# xbee_module_jan2022.net
KiCad netlist of a schematic drawn in EAGLE
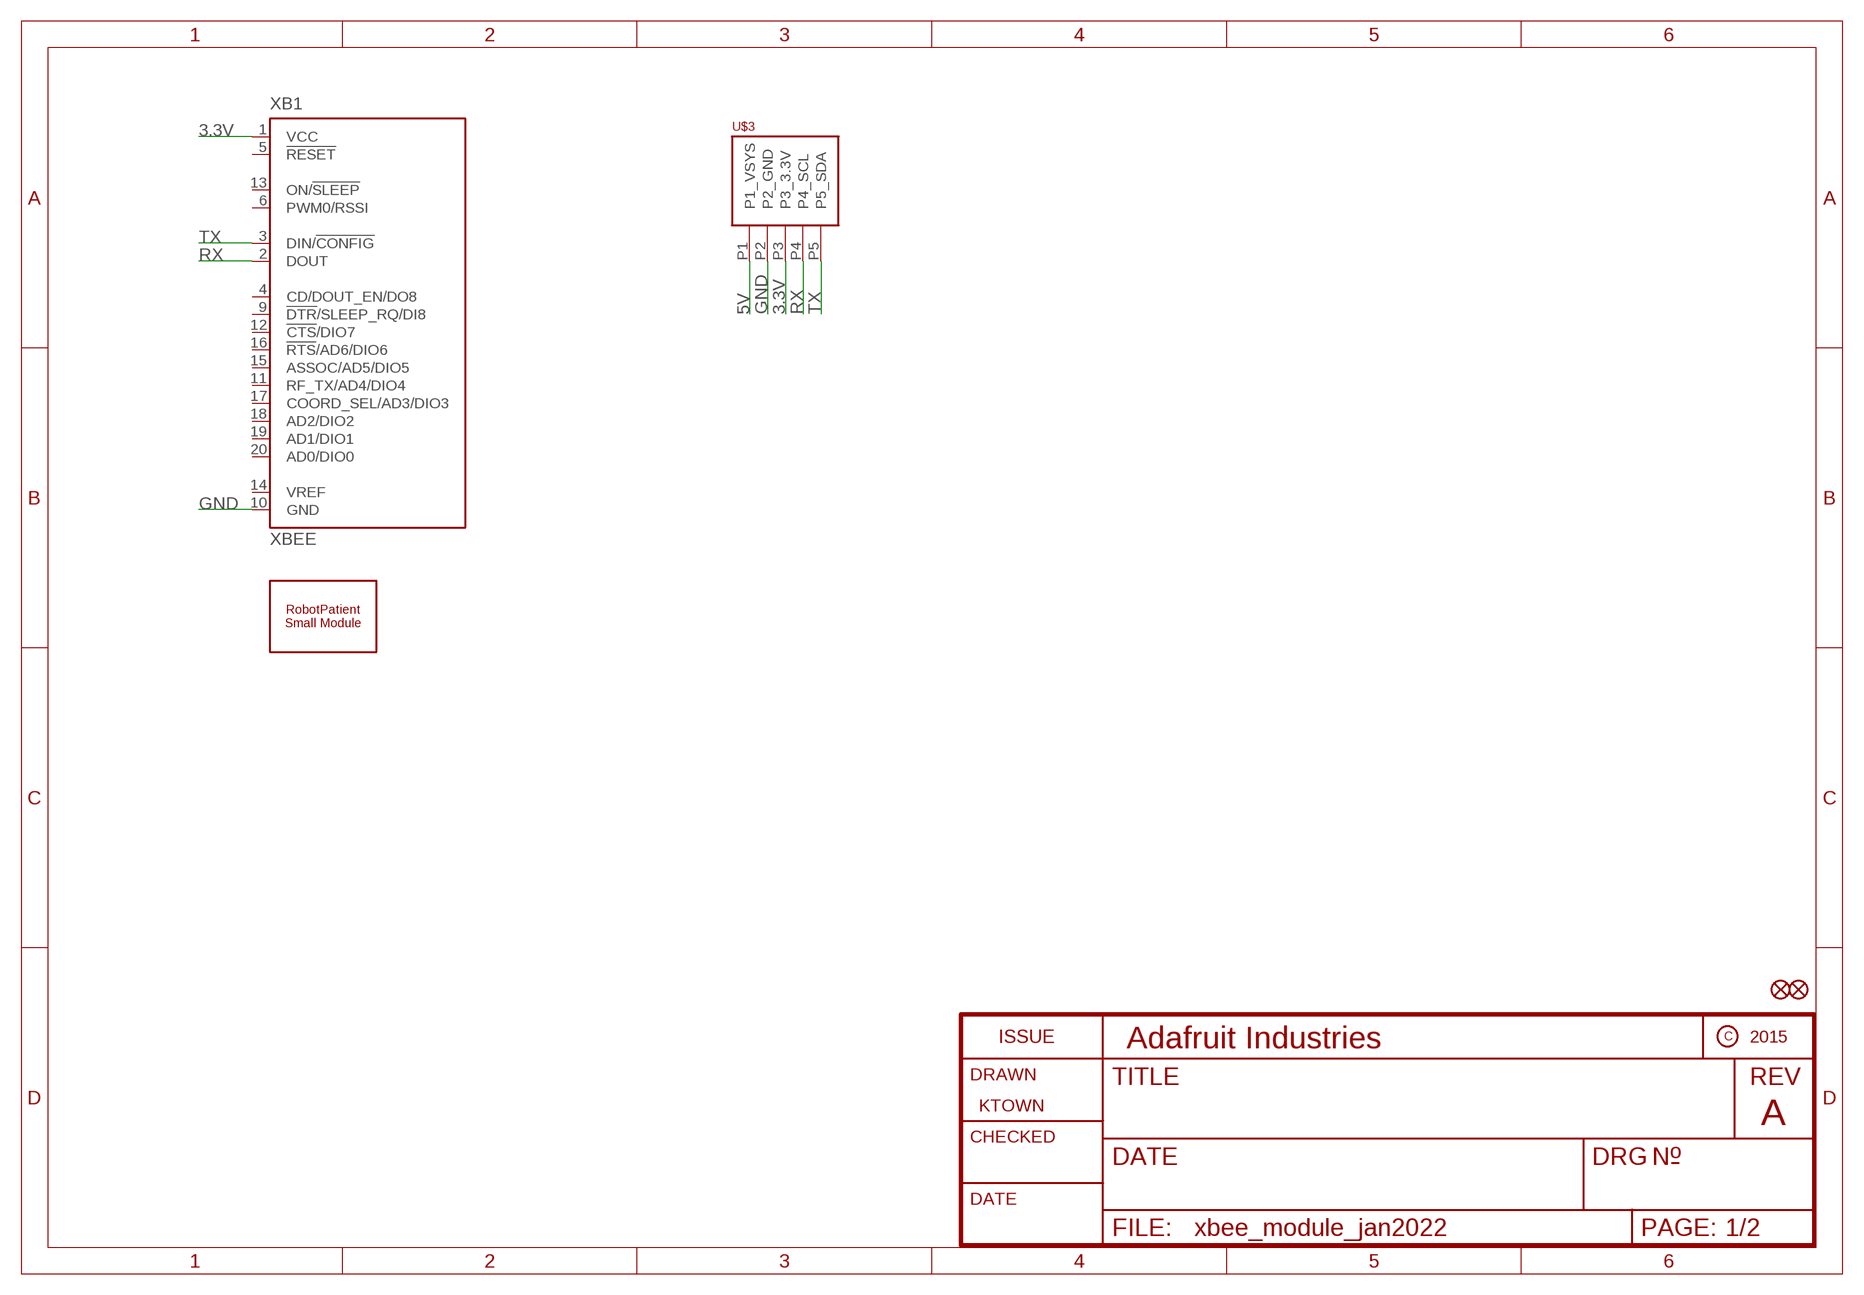
[diagram p0: schematic, sheet 1]
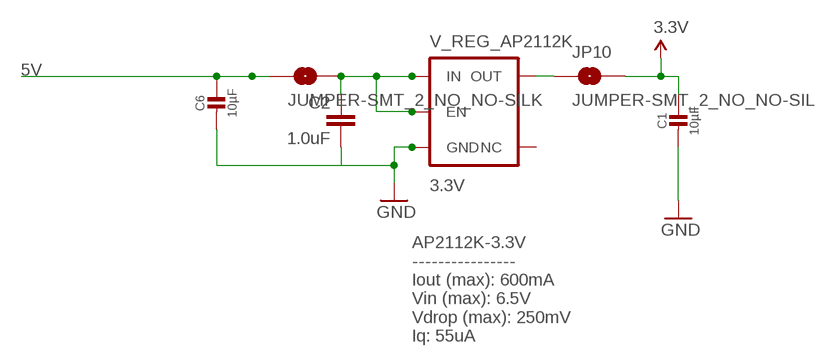
[diagram p1: schematic, sheet 2]

(export (version "E")
  (design (tool "Eeschema 10.0.6"))
  (components
    (comp (ref "FID1")
      (value "FIDUCIAL\"\"")
      (footprint "eagle-import:FIDUCIAL_1MM")
      (libsource (lib "eagle-import") (part "FIDUCIAL{dblquote}{dblquote}"))
    )
    (comp (ref "FID2")
      (value "FIDUCIAL\"\"")
      (footprint "eagle-import:FIDUCIAL_1MM")
      (libsource (lib "eagle-import") (part "FIDUCIAL{dblquote}{dblquote}"))
    )
    (comp (ref "U$2")
      (value "ROBOTPATIENT_SMALL_MODULEBOARD")
      (footprint "eagle-import:RP_SMALL_SENSOR_OUTLINE")
      (libsource (lib "eagle-import") (part "ROBOTPATIENT_SMALL_MODULEBOARD"))
    )
    (comp (ref "U$3")
      (value "PHOENIX_PTSM_M5_THUART")
      (footprint "eagle-import:PTSM_M5_TH_UART")
      (libsource (lib "eagle-import") (part "PHOENIX_PTSM_M5_THUART"))
    )
    (comp (ref "XB1")
      (value "XBEE")
      (footprint "eagle-import:XBEE")
      (fields (field (name "MPN") "XBP24-Z7UIT-004"))
      (libsource (lib "eagle-import") (part "XBEE"))
    )
    (comp (ref "C1")
      (value "10µF")
      (footprint "eagle-import:0805-NO")
      (libsource (lib "eagle-import") (part "CAP_CERAMIC0805-NOOUTLINE"))
    )
    (comp (ref "C2")
      (value "1.0uF")
      (footprint "eagle-import:0805-CAP")
      (libsource (lib "eagle-import") (part "1.0UF-25V-+80/-20(0805){dblquote}"))
    )
    (comp (ref "C6")
      (value "10µF")
      (footprint "eagle-import:0805-NO")
      (libsource (lib "eagle-import") (part "CAP_CERAMIC0805-NOOUTLINE"))
    )
    (comp (ref "JP10")
      (value "JUMPER-SMT_2_NO_NO-SILK")
      (footprint "eagle-import:SMT-JUMPER_2_NO_NO-SILK")
      (libsource (lib "eagle-import") (part "JUMPER-SMT_2_NO_NO-SILK"))
    )
    (comp (ref "JP11")
      (value "JUMPER-SMT_2_NO_NO-SILK")
      (footprint "eagle-import:SMT-JUMPER_2_NO_NO-SILK")
      (libsource (lib "eagle-import") (part "JUMPER-SMT_2_NO_NO-SILK"))
    )
    (comp (ref "V_REG_AP2112K")
      (value "3.3V")
      (footprint "eagle-import:SOT23-5")
      (libsource (lib "eagle-import") (part "V_REG_AP2112K-3.3V"))
    )
  )
  (nets
    (net (code "1") (name "3.3V") (class "Default")
      (node (ref "C1") (pin "1") (pinfunction "1_1") (pintype "passive"))
      (node (ref "JP10") (pin "2") (pinfunction "2_2") (pintype "passive"))
      (node (ref "U$3") (pin "P3") (pinfunction "P3_3.3V_P3") (pintype "power_in"))
      (node (ref "XB1") (pin "1") (pinfunction "VCC_1") (pintype "power_in"))
    )
    (net (code "2") (name "5V") (class "Default")
      (node (ref "C6") (pin "1") (pinfunction "1_1") (pintype "passive"))
      (node (ref "JP11") (pin "1") (pinfunction "1_1") (pintype "passive"))
      (node (ref "U$3") (pin "P1") (pinfunction "P1_VSYS_P1") (pintype "power_in"))
    )
    (net (code "3") (name "GND") (class "Default")
      (node (ref "C1") (pin "2") (pinfunction "2_2") (pintype "passive"))
      (node (ref "C2") (pin "2") (pinfunction "2_2") (pintype "passive"))
      (node (ref "C6") (pin "2") (pinfunction "2_2") (pintype "passive"))
      (node (ref "U$3") (pin "P2") (pinfunction "P2_GND_P2") (pintype "power_in"))
      (node (ref "V_REG_AP2112K") (pin "2") (pinfunction "GND_2") (pintype "input"))
      (node (ref "XB1") (pin "10") (pinfunction "GND_10") (pintype "power_in"))
    )
    (net (code "4") (name "Net-(V_REG_AP2112K-EN)") (class "Default")
      (node (ref "C2") (pin "1") (pinfunction "1_1") (pintype "passive"))
      (node (ref "JP11") (pin "2") (pinfunction "2_2") (pintype "passive"))
      (node (ref "V_REG_AP2112K") (pin "1") (pinfunction "IN_1") (pintype "input"))
      (node (ref "V_REG_AP2112K") (pin "3") (pinfunction "EN_3") (pintype "input"))
    )
    (net (code "5") (name "Net-(V_REG_AP2112K-OUT)") (class "Default")
      (node (ref "JP10") (pin "1") (pinfunction "1_1") (pintype "passive"))
      (node (ref "V_REG_AP2112K") (pin "5") (pinfunction "OUT_5") (pintype "passive"))
    )
    (net (code "6") (name "RX") (class "Default")
      (node (ref "U$3") (pin "P4") (pinfunction "P4_SCL_P4") (pintype "bidirectional"))
      (node (ref "XB1") (pin "2") (pinfunction "DOUT_2") (pintype "output"))
    )
    (net (code "7") (name "TX") (class "Default")
      (node (ref "U$3") (pin "P5") (pinfunction "P5_SDA_P5") (pintype "bidirectional"))
      (node (ref "XB1") (pin "3") (pinfunction "DIN/~{CONFIG}_3") (pintype "input"))
    )
    (net (code "8") (name "unconnected-(V_REG_AP2112K-NC-Pad4)") (class "Default")
      (node (ref "V_REG_AP2112K") (pin "4") (pinfunction "NC_4") (pintype "input"))
    )
    (net (code "9") (name "unconnected-(XB1-AD0{slash}DIO0-Pad20)") (class "Default")
      (node (ref "XB1") (pin "20") (pinfunction "AD0/DIO0_20") (pintype "bidirectional"))
    )
    (net (code "10") (name "unconnected-(XB1-AD1{slash}DIO1-Pad19)") (class "Default")
      (node (ref "XB1") (pin "19") (pinfunction "AD1/DIO1_19") (pintype "bidirectional"))
    )
    (net (code "11") (name "unconnected-(XB1-AD2{slash}DIO2-Pad18)") (class "Default")
      (node (ref "XB1") (pin "18") (pinfunction "AD2/DIO2_18") (pintype "bidirectional"))
    )
    (net (code "12") (name "unconnected-(XB1-ASSOC{slash}AD5{slash}DIO5-Pad15)") (class "Default")
      (node (ref "XB1") (pin "15") (pinfunction "ASSOC/AD5/DIO5_15") (pintype "bidirectional"))
    )
    (net (code "13") (name "unconnected-(XB1-CD{slash}DOUT_EN{slash}DO8-Pad4)") (class "Default")
      (node (ref "XB1") (pin "4") (pinfunction "CD/DOUT_EN/DO8_4") (pintype "output"))
    )
    (net (code "14") (name "unconnected-(XB1-COORD_SEL{slash}AD3{slash}DIO3-Pad17)") (class "Default")
      (node (ref "XB1") (pin "17") (pinfunction "COORD_SEL/AD3/DIO3_17") (pintype "bidirectional"))
    )
    (net (code "15") (name "unconnected-(XB1-ON{slash}~{SLEEP}-Pad13)") (class "Default")
      (node (ref "XB1") (pin "13") (pinfunction "ON/~{SLEEP}_13") (pintype "output"))
    )
    (net (code "16") (name "unconnected-(XB1-PWM0{slash}RSSI-Pad6)") (class "Default")
      (node (ref "XB1") (pin "6") (pinfunction "PWM0/RSSI_6") (pintype "output"))
    )
    (net (code "17") (name "unconnected-(XB1-RF_TX{slash}AD4{slash}DIO4-Pad11)") (class "Default")
      (node (ref "XB1") (pin "11") (pinfunction "RF_TX/AD4/DIO4_11") (pintype "bidirectional"))
    )
    (net (code "18") (name "unconnected-(XB1-VREF-Pad14)") (class "Default")
      (node (ref "XB1") (pin "14") (pinfunction "VREF_14") (pintype "input"))
    )
    (net (code "19") (name "unconnected-(XB1-~{CTS}{slash}DIO7-Pad12)") (class "Default")
      (node (ref "XB1") (pin "12") (pinfunction "~{CTS}/DIO7_12") (pintype "bidirectional"))
    )
    (net (code "20") (name "unconnected-(XB1-~{DTR}{slash}SLEEP_RQ{slash}DI8-Pad9)") (class "Default")
      (node (ref "XB1") (pin "9") (pinfunction "~{DTR}/SLEEP_RQ/DI8_9") (pintype "bidirectional"))
    )
    (net (code "21") (name "unconnected-(XB1-~{RESET}-Pad5)") (class "Default")
      (node (ref "XB1") (pin "5") (pinfunction "~{RESET}_5") (pintype "input"))
    )
    (net (code "22") (name "unconnected-(XB1-~{RTS}{slash}AD6{slash}DIO6-Pad16)") (class "Default")
      (node (ref "XB1") (pin "16") (pinfunction "~{RTS}/AD6/DIO6_16") (pintype "bidirectional"))
    )
  )
)
